# Sheet1.net
KiCad netlist of a schematic drawn in Altium Designer
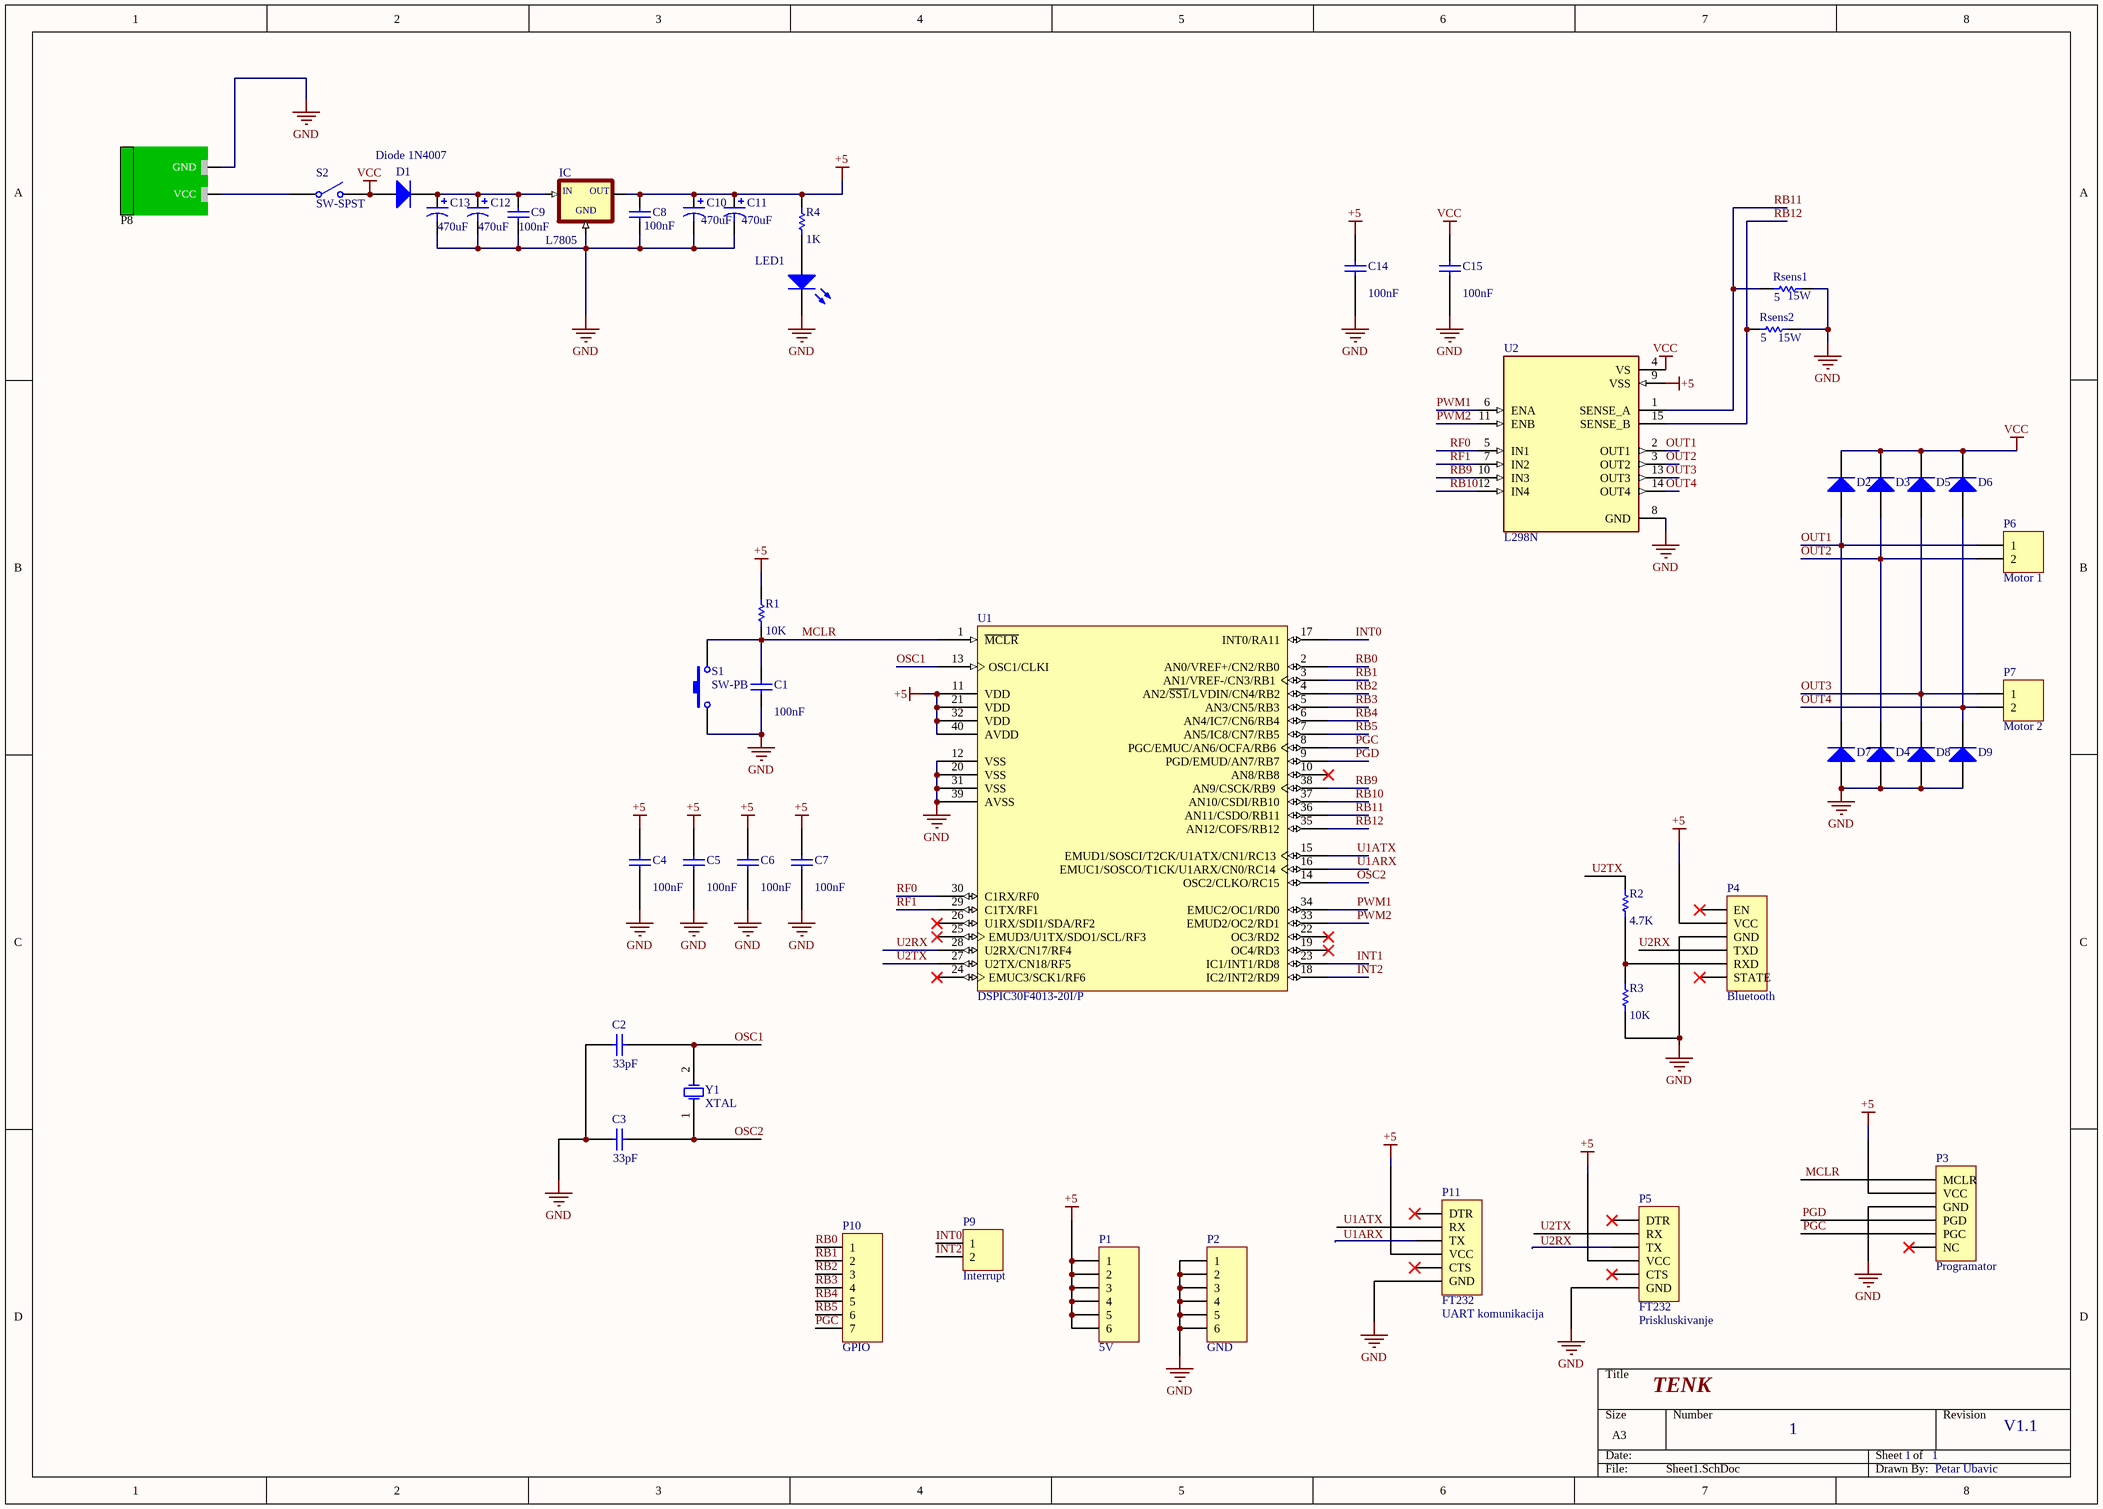
[diagram p0: Sheet1.SchDoc]

(export (version "E")
  (design (tool "Eeschema 10.0.6"))
  (components
    (comp (ref "C1")
      (value "100nF")
      (footprint "CAP200")
      (description "Capacitor")
      (fields (field (name "Comment") "Cap") (field (name "PUBLISHER") "Altium Limited"))
      (libsource (lib "Miscellaneous Devices") (part "Cap"))
    )
    (comp (ref "C2")
      (value "33pF")
      (footprint "CAP200")
      (description "Capacitor")
      (fields (field (name "Comment") "Cap") (field (name "PUBLISHER") "Altium Limited"))
      (libsource (lib "Miscellaneous Devices") (part "Cap"))
    )
    (comp (ref "C3")
      (value "33pF")
      (footprint "CAP200")
      (description "Capacitor")
      (fields (field (name "Comment") "Cap") (field (name "PUBLISHER") "Altium Limited"))
      (libsource (lib "Miscellaneous Devices") (part "Cap"))
    )
    (comp (ref "C4")
      (value "100nF")
      (footprint "CAP200")
      (description "Capacitor")
      (fields (field (name "Comment") "Cap") (field (name "PUBLISHER") "Altium Limited"))
      (libsource (lib "Miscellaneous Devices") (part "Cap"))
    )
    (comp (ref "C5")
      (value "100nF")
      (footprint "CAP200")
      (description "Capacitor")
      (fields (field (name "Comment") "Cap") (field (name "PUBLISHER") "Altium Limited"))
      (libsource (lib "Miscellaneous Devices") (part "Cap"))
    )
    (comp (ref "C6")
      (value "100nF")
      (footprint "CAP200")
      (description "Capacitor")
      (fields (field (name "Comment") "Cap") (field (name "PUBLISHER") "Altium Limited"))
      (libsource (lib "Miscellaneous Devices") (part "Cap"))
    )
    (comp (ref "C7")
      (value "100nF")
      (footprint "CAP200")
      (description "Capacitor")
      (fields (field (name "Comment") "Cap") (field (name "PUBLISHER") "Altium Limited"))
      (libsource (lib "Miscellaneous Devices") (part "Cap"))
    )
    (comp (ref "C8")
      (value "100nF")
      (footprint "CAP200")
      (description "Capacitor")
      (fields (field (name "Comment") "Cap") (field (name "PUBLISHER") "Altium Limited"))
      (libsource (lib "Miscellaneous Devices") (part "Cap"))
    )
    (comp (ref "C9")
      (value "100nF")
      (footprint "CAP200")
      (description "Capacitor")
      (fields (field (name "Comment") "Cap") (field (name "PUBLISHER") "Altium Limited"))
      (libsource (lib "Miscellaneous Devices") (part "Cap"))
    )
    (comp (ref "C10")
      (value "470uF")
      (footprint "RAD4")
      (description "Polarized Capacitor (Radial)")
      (fields (field (name "Comment") "Cap Pol1") (field (name "PUBLISHER") "Altium Limited"))
      (libsource (lib "Miscellaneous Devices") (part "Cap Pol1"))
    )
    (comp (ref "C11")
      (value "470uF")
      (footprint "RAD4")
      (description "Polarized Capacitor (Radial)")
      (fields (field (name "Comment") "Cap Pol1") (field (name "PUBLISHER") "Altium Limited"))
      (libsource (lib "Miscellaneous Devices") (part "Cap Pol1"))
    )
    (comp (ref "C12")
      (value "470uF")
      (footprint "RAD4")
      (description "Polarized Capacitor (Radial)")
      (fields (field (name "Comment") "Cap Pol1") (field (name "PUBLISHER") "Altium Limited"))
      (libsource (lib "Miscellaneous Devices") (part "Cap Pol1"))
    )
    (comp (ref "C13")
      (value "470uF")
      (footprint "RAD4")
      (description "Polarized Capacitor (Radial)")
      (fields (field (name "Comment") "Cap Pol1") (field (name "PUBLISHER") "Altium Limited"))
      (libsource (lib "Miscellaneous Devices") (part "Cap Pol1"))
    )
    (comp (ref "C14")
      (value "100nF")
      (footprint "CAP200")
      (description "Capacitor")
      (fields (field (name "Comment") "Cap") (field (name "PUBLISHER") "Altium Limited"))
      (libsource (lib "Miscellaneous Devices") (part "Cap"))
    )
    (comp (ref "C15")
      (value "100nF")
      (footprint "CAP200")
      (description "Capacitor")
      (fields (field (name "Comment") "Cap") (field (name "PUBLISHER") "Altium Limited"))
      (libsource (lib "Miscellaneous Devices") (part "Cap"))
    )
    (comp (ref "D1")
      (value "Diode 1N4007")
      (footprint "DIODE400")
      (description "1 Amp General Purpose Rectifier")
      (fields (field (name "PUBLISHER") "Altium Limited"))
      (libsource (lib "Miscellaneous Devices") (part "Diode 1N4007"))
    )
    (comp (ref "D2")
      (value "Diode 1N5402")
      (footprint "DIODE400")
      (description "3 Amp General Purpose Rectifier")
      (fields (field (name "PUBLISHER") "Altium Limited"))
      (libsource (lib "Miscellaneous Devices") (part "Diode 1N5402"))
    )
    (comp (ref "D3")
      (value "Diode 1N5402")
      (footprint "DIODE400")
      (description "3 Amp General Purpose Rectifier")
      (fields (field (name "PUBLISHER") "Altium Limited"))
      (libsource (lib "Miscellaneous Devices") (part "Diode 1N5402"))
    )
    (comp (ref "D4")
      (value "Diode 1N5402")
      (footprint "DIODE400")
      (description "3 Amp General Purpose Rectifier")
      (fields (field (name "PUBLISHER") "Altium Limited"))
      (libsource (lib "Miscellaneous Devices") (part "Diode 1N5402"))
    )
    (comp (ref "D5")
      (value "Diode 1N5402")
      (footprint "DIODE400")
      (description "3 Amp General Purpose Rectifier")
      (fields (field (name "PUBLISHER") "Altium Limited"))
      (libsource (lib "Miscellaneous Devices") (part "Diode 1N5402"))
    )
    (comp (ref "D6")
      (value "Diode 1N5402")
      (footprint "DIODE400")
      (description "3 Amp General Purpose Rectifier")
      (fields (field (name "PUBLISHER") "Altium Limited"))
      (libsource (lib "Miscellaneous Devices") (part "Diode 1N5402"))
    )
    (comp (ref "D7")
      (value "Diode 1N5402")
      (footprint "DIODE400")
      (description "3 Amp General Purpose Rectifier")
      (fields (field (name "PUBLISHER") "Altium Limited"))
      (libsource (lib "Miscellaneous Devices") (part "Diode 1N5402"))
    )
    (comp (ref "D8")
      (value "Diode 1N5402")
      (footprint "DIODE400")
      (description "3 Amp General Purpose Rectifier")
      (fields (field (name "PUBLISHER") "Altium Limited"))
      (libsource (lib "Miscellaneous Devices") (part "Diode 1N5402"))
    )
    (comp (ref "D9")
      (value "Diode 1N5402")
      (footprint "DIODE400")
      (description "3 Amp General Purpose Rectifier")
      (fields (field (name "PUBLISHER") "Altium Limited"))
      (libsource (lib "Miscellaneous Devices") (part "Diode 1N5402"))
    )
    (comp (ref "IC")
      (value "L7805")
      (footprint "78XXS")
      (description "Linear Voltage Regulator IC 1 Output 1.5A D2PAK")
      (fields (field (name "MF") "STMicroelectronics"))
      (libsource (lib "L7805") (part "L7805"))
    )
    (comp (ref "LED1")
      (value "GREEN")
      (footprint "LED_2")
      (description "Typical RED GaAs LED")
      (fields (field (name "PUBLISHER") "Altium Limited"))
      (libsource (lib "Miscellaneous Devices") (part "LED1"))
    )
    (comp (ref "P1")
      (value "5V")
      (footprint "HEADER_6")
      (description "Header, 6-Pin")
      (fields (field (name "PUBLISHER") "Altium Limited"))
      (libsource (lib "Miscellaneous Connectors") (part "Header 6"))
    )
    (comp (ref "P2")
      (value "GND")
      (footprint "HEADER_6")
      (description "Header, 6-Pin")
      (fields (field (name "PUBLISHER") "Altium Limited"))
      (libsource (lib "Miscellaneous Connectors") (part "Header 6"))
    )
    (comp (ref "P3")
      (value "Programator")
      (footprint "HEADER_6")
      (description "Header, 6-Pin")
      (fields (field (name "PUBLISHER") "Altium Limited"))
      (libsource (lib "Miscellaneous Connectors") (part "Header 6"))
    )
    (comp (ref "P4")
      (value "Bluetooth")
      (footprint "HEADER_6")
      (description "Header, 6-Pin")
      (fields (field (name "PUBLISHER") "Altium Limited"))
      (libsource (lib "Miscellaneous Connectors") (part "Header 6"))
    )
    (comp (ref "P5")
      (value "FT232")
      (footprint "HEADER_6")
      (description "Header, 6-Pin")
      (fields (field (name "PUBLISHER") "Altium Limited"))
      (libsource (lib "Miscellaneous Connectors") (part "Header 6"))
    )
    (comp (ref "P6")
      (value "Motor 1")
      (footprint "HDR1X2")
      (description "Header, 2-Pin")
      (fields (field (name "PUBLISHER") "Altium Limited"))
      (libsource (lib "Miscellaneous Connectors") (part "Header 2"))
    )
    (comp (ref "P7")
      (value "Motor 2")
      (footprint "HDR1X2")
      (description "Header, 2-Pin")
      (fields (field (name "PUBLISHER") "Altium Limited"))
      (libsource (lib "Miscellaneous Connectors") (part "Header 2"))
    )
    (comp (ref "P8")
      (value "2EDGRC-5.08-02P-14-00A(H)")
      (footprint "PWR_Con")
      (description "TERM BLOCK HDR 2POS 90DEG 5.08MM")
      (libsource (lib "Electro_Mechanical") (part "00000002"))
    )
    (comp (ref "P9")
      (value "Interrupt")
      (footprint "HDR1X2")
      (description "Header, 2-Pin")
      (fields (field (name "PUBLISHER") "Altium Limited"))
      (libsource (lib "Miscellaneous Connectors") (part "Header 2"))
    )
    (comp (ref "P10")
      (value "GPIO")
      (footprint "HDR1X7")
      (description "Header, 7-Pin")
      (fields (field (name "PUBLISHER") "Altium Limited"))
      (libsource (lib "Miscellaneous Connectors") (part "Header 7"))
    )
    (comp (ref "P11")
      (value "FT232")
      (footprint "HEADER_6")
      (description "Header, 6-Pin")
      (fields (field (name "PUBLISHER") "Altium Limited"))
      (libsource (lib "Miscellaneous Connectors") (part "Header 6"))
    )
    (comp (ref "R1")
      (value "10K")
      (footprint "RES400")
      (description "Resistor")
      (fields (field (name "Comment") "Res1") (field (name "PUBLISHER") "Altium Limited"))
      (libsource (lib "Miscellaneous Devices") (part "Res1"))
    )
    (comp (ref "R2")
      (value "4.7K")
      (footprint "RES400")
      (description "Resistor")
      (fields (field (name "Comment") "Res1") (field (name "PUBLISHER") "Altium Limited"))
      (libsource (lib "Miscellaneous Devices") (part "Res1"))
    )
    (comp (ref "R3")
      (value "10K")
      (footprint "RES400")
      (description "Resistor")
      (fields (field (name "Comment") "Res1") (field (name "PUBLISHER") "Altium Limited"))
      (libsource (lib "Miscellaneous Devices") (part "Res1"))
    )
    (comp (ref "R4")
      (value "1K")
      (footprint "RES400")
      (description "Resistor")
      (fields (field (name "Comment") "Res1") (field (name "PUBLISHER") "Altium Limited"))
      (libsource (lib "Miscellaneous Devices") (part "Res1"))
    )
    (comp (ref "Rsens1")
      (value "15W")
      (footprint "DIOAD1898W129L762D1143")
      (description "Resistor")
      (fields (field (name "ALTIUM_VALUE") "5") (field (name "PUBLISHER") "Altium Limited"))
      (libsource (lib "Miscellaneous Devices") (part "Res1"))
    )
    (comp (ref "Rsens2")
      (value "15W")
      (footprint "DIOAD1898W129L762D1143")
      (description "Resistor")
      (fields (field (name "ALTIUM_VALUE") "5") (field (name "PUBLISHER") "Altium Limited"))
      (libsource (lib "Miscellaneous Devices") (part "Res1"))
    )
    (comp (ref "S1")
      (value "SW-PB")
      (footprint "SPST-2")
      (description "Switch")
      (fields (field (name "PUBLISHER") "Altium Limited"))
      (libsource (lib "Miscellaneous Devices") (part "SW-PB"))
    )
    (comp (ref "S2")
      (value "SW-SPST")
      (footprint "CAP200")
      (description "Single-Pole, Single-Throw Switch")
      (fields (field (name "PUBLISHER") "Altium Limited"))
      (libsource (lib "Miscellaneous Devices") (part "SW-SPST"))
    )
    (comp (ref "U1")
      (value "DSPIC30F4013-20I/P")
      (footprint "PDIP600-P40")
      (fields (field (name "PUBLISHER") "Altium Limited"))
      (libsource (lib "Microchip DSC 16-Bit dsPIC30F") (part "DSPIC30F4013-20I/P"))
    )
    (comp (ref "U2")
      (value "L298N")
      (footprint "TO127P2020X500X2100-15")
      (description "Dual Full Bridge Motor Driver 15-Pin(15+Tab) MULTIWATT V Tube")
      (libsource (lib "L298N") (part "L298N"))
    )
    (comp (ref "Y1")
      (value "XTAL")
      (footprint "OSC_5")
      (description "Crystal Oscillator")
      (fields (field (name "PUBLISHER") "Altium Limited"))
      (libsource (lib "Miscellaneous Devices") (part "XTAL"))
    )
  )
  (nets
    (net (code "1") (name "+5") (class "Default")
      (node (ref "C10") (pin "1") (pinfunction "1_1") (pintype "passive"))
      (node (ref "C11") (pin "1") (pinfunction "1_1") (pintype "passive"))
      (node (ref "C14") (pin "2") (pinfunction "2_2") (pintype "passive"))
      (node (ref "C4") (pin "2") (pinfunction "2_2") (pintype "passive"))
      (node (ref "C5") (pin "2") (pinfunction "2_2") (pintype "passive"))
      (node (ref "C6") (pin "2") (pinfunction "2_2") (pintype "passive"))
      (node (ref "C7") (pin "2") (pinfunction "2_2") (pintype "passive"))
      (node (ref "C8") (pin "2") (pinfunction "2_2") (pintype "passive"))
      (node (ref "IC") (pin "OUT") (pinfunction "OUT_OUT") (pintype "passive"))
      (node (ref "P1") (pin "1") (pinfunction "MCLR_1") (pintype "passive"))
      (node (ref "P1") (pin "2") (pinfunction "VCC_2") (pintype "passive"))
      (node (ref "P1") (pin "3") (pinfunction "GND_3") (pintype "passive"))
      (node (ref "P1") (pin "4") (pinfunction "PGD_4") (pintype "passive"))
      (node (ref "P1") (pin "5") (pinfunction "PGC_5") (pintype "passive"))
      (node (ref "P1") (pin "6") (pinfunction "NC_6") (pintype "passive"))
      (node (ref "P11") (pin "4") (pinfunction "PGD_4") (pintype "passive"))
      (node (ref "P3") (pin "2") (pinfunction "VCC_2") (pintype "passive"))
      (node (ref "P4") (pin "2") (pinfunction "VCC_2") (pintype "passive"))
      (node (ref "P5") (pin "4") (pinfunction "PGD_4") (pintype "passive"))
      (node (ref "R1") (pin "2") (pinfunction "2_2") (pintype "passive"))
      (node (ref "R4") (pin "2") (pinfunction "2_2") (pintype "passive"))
      (node (ref "U1") (pin "11") (pinfunction "VDD_11") (pintype "power_in"))
      (node (ref "U1") (pin "21") (pinfunction "VDD_21") (pintype "power_in"))
      (node (ref "U1") (pin "32") (pinfunction "VDD_32") (pintype "power_in"))
      (node (ref "U1") (pin "40") (pinfunction "AVDD_40") (pintype "power_in"))
      (node (ref "U2") (pin "9") (pinfunction "VSS_9") (pintype "input"))
    )
    (net (code "2") (name "/INT0") (class "Default")
      (node (ref "P9") (pin "1") (pinfunction "1_1") (pintype "passive"))
      (node (ref "U1") (pin "17") (pinfunction "INT0/RA11_17") (pintype "bidirectional"))
    )
    (net (code "3") (name "/INT1") (class "Default")
      (node (ref "U1") (pin "23") (pinfunction "IC1/INT1/RD8_23") (pintype "bidirectional"))
    )
    (net (code "4") (name "/INT2") (class "Default")
      (node (ref "P9") (pin "2") (pinfunction "2_2") (pintype "passive"))
      (node (ref "U1") (pin "18") (pinfunction "IC2/INT2/RD9_18") (pintype "bidirectional"))
    )
    (net (code "5") (name "/MCLR") (class "Default")
      (node (ref "C1") (pin "2") (pinfunction "2_2") (pintype "passive"))
      (node (ref "P3") (pin "1") (pinfunction "MCLR_1") (pintype "passive"))
      (node (ref "R1") (pin "1") (pinfunction "1_1") (pintype "passive"))
      (node (ref "S1") (pin "2") (pinfunction "2_2") (pintype "passive"))
      (node (ref "U1") (pin "1") (pinfunction "~{MCLR}_1") (pintype "input"))
    )
    (net (code "6") (name "/OSC1") (class "Default")
      (node (ref "C2") (pin "2") (pinfunction "2_2") (pintype "passive"))
      (node (ref "U1") (pin "13") (pinfunction "OSC1/CLKI_13") (pintype "input"))
      (node (ref "Y1") (pin "2") (pinfunction "OSC2_2") (pintype "passive"))
    )
    (net (code "7") (name "/OSC2") (class "Default")
      (node (ref "C3") (pin "2") (pinfunction "2_2") (pintype "passive"))
      (node (ref "U1") (pin "14") (pinfunction "OSC2/CLKO/RC15_14") (pintype "bidirectional"))
      (node (ref "Y1") (pin "1") (pinfunction "OSC1_1") (pintype "passive"))
    )
    (net (code "8") (name "/OUT1") (class "Default")
      (node (ref "D2") (pin "1") (pinfunction "A_1") (pintype "passive"))
      (node (ref "D7") (pin "2") (pinfunction "K_2") (pintype "passive"))
      (node (ref "P6") (pin "1") (pinfunction "1_1") (pintype "passive"))
      (node (ref "U2") (pin "2") (pinfunction "OUT1_2") (pintype "output"))
    )
    (net (code "9") (name "/OUT2") (class "Default")
      (node (ref "D3") (pin "1") (pinfunction "A_1") (pintype "passive"))
      (node (ref "D4") (pin "2") (pinfunction "K_2") (pintype "passive"))
      (node (ref "P6") (pin "2") (pinfunction "2_2") (pintype "passive"))
      (node (ref "U2") (pin "3") (pinfunction "OUT2_3") (pintype "output"))
    )
    (net (code "10") (name "/OUT3") (class "Default")
      (node (ref "D5") (pin "1") (pinfunction "A_1") (pintype "passive"))
      (node (ref "D8") (pin "2") (pinfunction "K_2") (pintype "passive"))
      (node (ref "P7") (pin "1") (pinfunction "1_1") (pintype "passive"))
      (node (ref "U2") (pin "13") (pinfunction "OUT3_13") (pintype "output"))
    )
    (net (code "11") (name "/OUT4") (class "Default")
      (node (ref "D6") (pin "1") (pinfunction "A_1") (pintype "passive"))
      (node (ref "D9") (pin "2") (pinfunction "K_2") (pintype "passive"))
      (node (ref "P7") (pin "2") (pinfunction "2_2") (pintype "passive"))
      (node (ref "U2") (pin "14") (pinfunction "OUT4_14") (pintype "output"))
    )
    (net (code "12") (name "/PGC") (class "Default")
      (node (ref "P10") (pin "7") (pinfunction "7_7") (pintype "passive"))
      (node (ref "P3") (pin "5") (pinfunction "PGC_5") (pintype "passive"))
      (node (ref "U1") (pin "8") (pinfunction "PGC/EMUC/AN6/OCFA/RB6_8") (pintype "bidirectional"))
    )
    (net (code "13") (name "/PGD") (class "Default")
      (node (ref "P3") (pin "4") (pinfunction "PGD_4") (pintype "passive"))
      (node (ref "U1") (pin "9") (pinfunction "PGD/EMUD/AN7/RB7_9") (pintype "bidirectional"))
    )
    (net (code "14") (name "/PWM1") (class "Default")
      (node (ref "U1") (pin "34") (pinfunction "EMUC2/OC1/RD0_34") (pintype "bidirectional"))
      (node (ref "U2") (pin "6") (pinfunction "ENA_6") (pintype "input"))
    )
    (net (code "15") (name "/PWM2") (class "Default")
      (node (ref "U1") (pin "33") (pinfunction "EMUD2/OC2/RD1_33") (pintype "bidirectional"))
      (node (ref "U2") (pin "11") (pinfunction "ENB_11") (pintype "input"))
    )
    (net (code "16") (name "/RB0") (class "Default")
      (node (ref "P10") (pin "1") (pinfunction "1_1") (pintype "passive"))
      (node (ref "U1") (pin "2") (pinfunction "AN0/VREF+/CN2/RB0_2") (pintype "bidirectional"))
    )
    (net (code "17") (name "/RB1") (class "Default")
      (node (ref "P10") (pin "2") (pinfunction "2_2") (pintype "passive"))
      (node (ref "U1") (pin "3") (pinfunction "AN1/VREF-/CN3/RB1_3") (pintype "bidirectional"))
    )
    (net (code "18") (name "/RB2") (class "Default")
      (node (ref "P10") (pin "3") (pinfunction "3_3") (pintype "passive"))
      (node (ref "U1") (pin "4") (pinfunction "AN2/~{SS1}/LVDIN/CN4/RB2_4") (pintype "bidirectional"))
    )
    (net (code "19") (name "/RB3") (class "Default")
      (node (ref "P10") (pin "4") (pinfunction "4_4") (pintype "passive"))
      (node (ref "U1") (pin "5") (pinfunction "AN3/CN5/RB3_5") (pintype "bidirectional"))
    )
    (net (code "20") (name "/RB4") (class "Default")
      (node (ref "P10") (pin "5") (pinfunction "5_5") (pintype "passive"))
      (node (ref "U1") (pin "6") (pinfunction "AN4/IC7/CN6/RB4_6") (pintype "bidirectional"))
    )
    (net (code "21") (name "/RB5") (class "Default")
      (node (ref "P10") (pin "6") (pinfunction "6_6") (pintype "passive"))
      (node (ref "U1") (pin "7") (pinfunction "AN5/IC8/CN7/RB5_7") (pintype "bidirectional"))
    )
    (net (code "22") (name "/RB9") (class "Default")
      (node (ref "U1") (pin "38") (pinfunction "AN9/CSCK/RB9_38") (pintype "bidirectional"))
      (node (ref "U2") (pin "10") (pinfunction "IN3_10") (pintype "input"))
    )
    (net (code "23") (name "/RB10") (class "Default")
      (node (ref "U1") (pin "37") (pinfunction "AN10/CSDI/RB10_37") (pintype "bidirectional"))
      (node (ref "U2") (pin "12") (pinfunction "IN4_12") (pintype "input"))
    )
    (net (code "24") (name "/RB11") (class "Default")
      (node (ref "Rsens1") (pin "1") (pinfunction "1_1") (pintype "passive"))
      (node (ref "U1") (pin "36") (pinfunction "AN11/CSDO/RB11_36") (pintype "bidirectional"))
      (node (ref "U2") (pin "1") (pinfunction "SENSE_A_1") (pintype "passive"))
    )
    (net (code "25") (name "/RB12") (class "Default")
      (node (ref "Rsens2") (pin "1") (pinfunction "1_1") (pintype "passive"))
      (node (ref "U1") (pin "35") (pinfunction "AN12/COFS/RB12_35") (pintype "bidirectional"))
      (node (ref "U2") (pin "15") (pinfunction "SENSE_B_15") (pintype "passive"))
    )
    (net (code "26") (name "/RF0") (class "Default")
      (node (ref "U1") (pin "30") (pinfunction "C1RX/RF0_30") (pintype "bidirectional"))
      (node (ref "U2") (pin "5") (pinfunction "IN1_5") (pintype "input"))
    )
    (net (code "27") (name "/RF1") (class "Default")
      (node (ref "U1") (pin "29") (pinfunction "C1TX/RF1_29") (pintype "bidirectional"))
      (node (ref "U2") (pin "7") (pinfunction "IN2_7") (pintype "input"))
    )
    (net (code "28") (name "/U1ARX") (class "Default")
      (node (ref "U1") (pin "16") (pinfunction "EMUC1/SOSCO/T1CK/U1ARX/CN0/RC14_16") (pintype "bidirectional"))
    )
    (net (code "29") (name "/U1ATX") (class "Default")
      (node (ref "P11") (pin "2") (pinfunction "VCC_2") (pintype "passive"))
      (node (ref "U1") (pin "15") (pinfunction "EMUD1/SOSCI/T2CK/U1ATX/CN1/RC13_15") (pintype "bidirectional"))
    )
    (net (code "30") (name "/U2RX") (class "Default")
      (node (ref "P4") (pin "4") (pinfunction "PGD_4") (pintype "passive"))
      (node (ref "U1") (pin "28") (pinfunction "U2RX/CN17/RF4_28") (pintype "bidirectional"))
    )
    (net (code "31") (name "/U2TX") (class "Default")
      (node (ref "P5") (pin "2") (pinfunction "VCC_2") (pintype "passive"))
      (node (ref "R2") (pin "2") (pinfunction "2_2") (pintype "passive"))
      (node (ref "U1") (pin "27") (pinfunction "U2TX/CN18/RF5_27") (pintype "bidirectional"))
    )
    (net (code "32") (name "GND") (class "Default")
      (node (ref "C1") (pin "1") (pinfunction "1_1") (pintype "passive"))
      (node (ref "C10") (pin "2") (pinfunction "2_2") (pintype "passive"))
      (node (ref "C11") (pin "2") (pinfunction "2_2") (pintype "passive"))
      (node (ref "C12") (pin "2") (pinfunction "2_2") (pintype "passive"))
      (node (ref "C13") (pin "2") (pinfunction "2_2") (pintype "passive"))
      (node (ref "C14") (pin "1") (pinfunction "1_1") (pintype "passive"))
      (node (ref "C15") (pin "1") (pinfunction "1_1") (pintype "passive"))
      (node (ref "C2") (pin "1") (pinfunction "1_1") (pintype "passive"))
      (node (ref "C3") (pin "1") (pinfunction "1_1") (pintype "passive"))
      (node (ref "C4") (pin "1") (pinfunction "1_1") (pintype "passive"))
      (node (ref "C5") (pin "1") (pinfunction "1_1") (pintype "passive"))
      (node (ref "C6") (pin "1") (pinfunction "1_1") (pintype "passive"))
      (node (ref "C7") (pin "1") (pinfunction "1_1") (pintype "passive"))
      (node (ref "C8") (pin "1") (pinfunction "1_1") (pintype "passive"))
      (node (ref "C9") (pin "1") (pinfunction "1_1") (pintype "passive"))
      (node (ref "D4") (pin "1") (pinfunction "A_1") (pintype "passive"))
      (node (ref "D7") (pin "1") (pinfunction "A_1") (pintype "passive"))
      (node (ref "D8") (pin "1") (pinfunction "A_1") (pintype "passive"))
      (node (ref "D9") (pin "1") (pinfunction "A_1") (pintype "passive"))
      (node (ref "IC") (pin "GND") (pinfunction "GND_GND") (pintype "input"))
      (node (ref "LED1") (pin "2") (pinfunction "K_2") (pintype "passive"))
      (node (ref "P11") (pin "6") (pinfunction "NC_6") (pintype "passive"))
      (node (ref "P2") (pin "1") (pinfunction "MCLR_1") (pintype "passive"))
      (node (ref "P2") (pin "2") (pinfunction "VCC_2") (pintype "passive"))
      (node (ref "P2") (pin "3") (pinfunction "GND_3") (pintype "passive"))
      (node (ref "P2") (pin "4") (pinfunction "PGD_4") (pintype "passive"))
      (node (ref "P2") (pin "5") (pinfunction "PGC_5") (pintype "passive"))
      (node (ref "P2") (pin "6") (pinfunction "NC_6") (pintype "passive"))
      (node (ref "P3") (pin "3") (pinfunction "GND_3") (pintype "passive"))
      (node (ref "P4") (pin "3") (pinfunction "GND_3") (pintype "passive"))
      (node (ref "P5") (pin "6") (pinfunction "NC_6") (pintype "passive"))
      (node (ref "P8") (pin "1") (pinfunction "GND_1") (pintype "passive"))
      (node (ref "R3") (pin "1") (pinfunction "1_1") (pintype "passive"))
      (node (ref "Rsens1") (pin "2") (pinfunction "2_2") (pintype "passive"))
      (node (ref "Rsens2") (pin "2") (pinfunction "2_2") (pintype "passive"))
      (node (ref "S1") (pin "1") (pinfunction "1_1") (pintype "passive"))
      (node (ref "U1") (pin "12") (pinfunction "VSS_12") (pintype "power_in"))
      (node (ref "U1") (pin "20") (pinfunction "VSS_20") (pintype "power_in"))
      (node (ref "U1") (pin "31") (pinfunction "VSS_31") (pintype "power_in"))
      (node (ref "U1") (pin "39") (pinfunction "AVSS_39") (pintype "power_in"))
      (node (ref "U2") (pin "8") (pinfunction "GND_8") (pintype "power_in"))
    )
    (net (code "33") (name "Net-(D1-K)") (class "Default")
      (node (ref "C12") (pin "1") (pinfunction "1_1") (pintype "passive"))
      (node (ref "C13") (pin "1") (pinfunction "1_1") (pintype "passive"))
      (node (ref "C9") (pin "2") (pinfunction "2_2") (pintype "passive"))
      (node (ref "D1") (pin "2") (pinfunction "K_2") (pintype "passive"))
      (node (ref "IC") (pin "IN") (pinfunction "IN_IN") (pintype "input"))
    )
    (net (code "34") (name "Net-(LED1-A)") (class "Default")
      (node (ref "LED1") (pin "1") (pinfunction "A_1") (pintype "passive"))
      (node (ref "R4") (pin "1") (pinfunction "1_1") (pintype "passive"))
    )
    (net (code "35") (name "Net-(P4-PGC)") (class "Default")
      (node (ref "P4") (pin "5") (pinfunction "PGC_5") (pintype "passive"))
      (node (ref "R2") (pin "1") (pinfunction "1_1") (pintype "passive"))
      (node (ref "R3") (pin "2") (pinfunction "2_2") (pintype "passive"))
    )
    (net (code "36") (name "Net-(P8-VCC)") (class "Default")
      (node (ref "P8") (pin "2") (pinfunction "VCC_2") (pintype "passive"))
      (node (ref "S2") (pin "1") (pinfunction "COMMON_1") (pintype "passive"))
    )
    (net (code "37") (name "VCC") (class "Default")
      (node (ref "C15") (pin "2") (pinfunction "2_2") (pintype "passive"))
      (node (ref "D1") (pin "1") (pinfunction "A_1") (pintype "passive"))
      (node (ref "D2") (pin "2") (pinfunction "K_2") (pintype "passive"))
      (node (ref "D3") (pin "2") (pinfunction "K_2") (pintype "passive"))
      (node (ref "D5") (pin "2") (pinfunction "K_2") (pintype "passive"))
      (node (ref "D6") (pin "2") (pinfunction "K_2") (pintype "passive"))
      (node (ref "S2") (pin "2") (pinfunction "NO_2") (pintype "passive"))
      (node (ref "U2") (pin "4") (pinfunction "VS_4") (pintype "power_in"))
    )
    (net (code "38") (name "unconnected-(P3-NC-Pad6)") (class "Default")
      (node (ref "P3") (pin "6") (pinfunction "NC_6") (pintype "passive+no_connect"))
    )
    (net (code "39") (name "unconnected-(P4-MCLR-Pad1)") (class "Default")
      (node (ref "P4") (pin "1") (pinfunction "MCLR_1") (pintype "passive+no_connect"))
    )
    (net (code "40") (name "unconnected-(P4-NC-Pad6)") (class "Default")
      (node (ref "P4") (pin "6") (pinfunction "NC_6") (pintype "passive+no_connect"))
    )
    (net (code "41") (name "unconnected-(P5-GND-Pad3)") (class "Default")
      (node (ref "P5") (pin "3") (pinfunction "GND_3") (pintype "passive"))
    )
    (net (code "42") (name "unconnected-(P5-MCLR-Pad1)") (class "Default")
      (node (ref "P5") (pin "1") (pinfunction "MCLR_1") (pintype "passive+no_connect"))
    )
    (net (code "43") (name "unconnected-(P5-PGC-Pad5)") (class "Default")
      (node (ref "P5") (pin "5") (pinfunction "PGC_5") (pintype "passive+no_connect"))
    )
    (net (code "44") (name "unconnected-(P11-GND-Pad3)") (class "Default")
      (node (ref "P11") (pin "3") (pinfunction "GND_3") (pintype "passive"))
    )
    (net (code "45") (name "unconnected-(P11-MCLR-Pad1)") (class "Default")
      (node (ref "P11") (pin "1") (pinfunction "MCLR_1") (pintype "passive+no_connect"))
    )
    (net (code "46") (name "unconnected-(P11-PGC-Pad5)") (class "Default")
      (node (ref "P11") (pin "5") (pinfunction "PGC_5") (pintype "passive+no_connect"))
    )
    (net (code "47") (name "unconnected-(U1-AN8{slash}RB8-Pad10)") (class "Default")
      (node (ref "U1") (pin "10") (pinfunction "AN8/RB8_10") (pintype "bidirectional+no_connect"))
    )
    (net (code "48") (name "unconnected-(U1-EMUC3{slash}SCK1{slash}RF6-Pad24)") (class "Default")
      (node (ref "U1") (pin "24") (pinfunction "EMUC3/SCK1/RF6_24") (pintype "bidirectional+no_connect"))
    )
    (net (code "49") (name "unconnected-(U1-EMUD3{slash}U1TX{slash}SDO1{slash}SCL{slash}RF3-Pad25)") (class "Default")
      (node (ref "U1") (pin "25") (pinfunction "EMUD3/U1TX/SDO1/SCL/RF3_25") (pintype "bidirectional+no_connect"))
    )
    (net (code "50") (name "unconnected-(U1-OC3{slash}RD2-Pad22)") (class "Default")
      (node (ref "U1") (pin "22") (pinfunction "OC3/RD2_22") (pintype "bidirectional+no_connect"))
    )
    (net (code "51") (name "unconnected-(U1-OC4{slash}RD3-Pad19)") (class "Default")
      (node (ref "U1") (pin "19") (pinfunction "OC4/RD3_19") (pintype "bidirectional+no_connect"))
    )
    (net (code "52") (name "unconnected-(U1-U1RX{slash}SDI1{slash}SDA{slash}RF2-Pad26)") (class "Default")
      (node (ref "U1") (pin "26") (pinfunction "U1RX/SDI1/SDA/RF2_26") (pintype "bidirectional+no_connect"))
    )
  )
)
